# led-headlamp.net
KiCad netlist of a schematic drawn in EAGLE
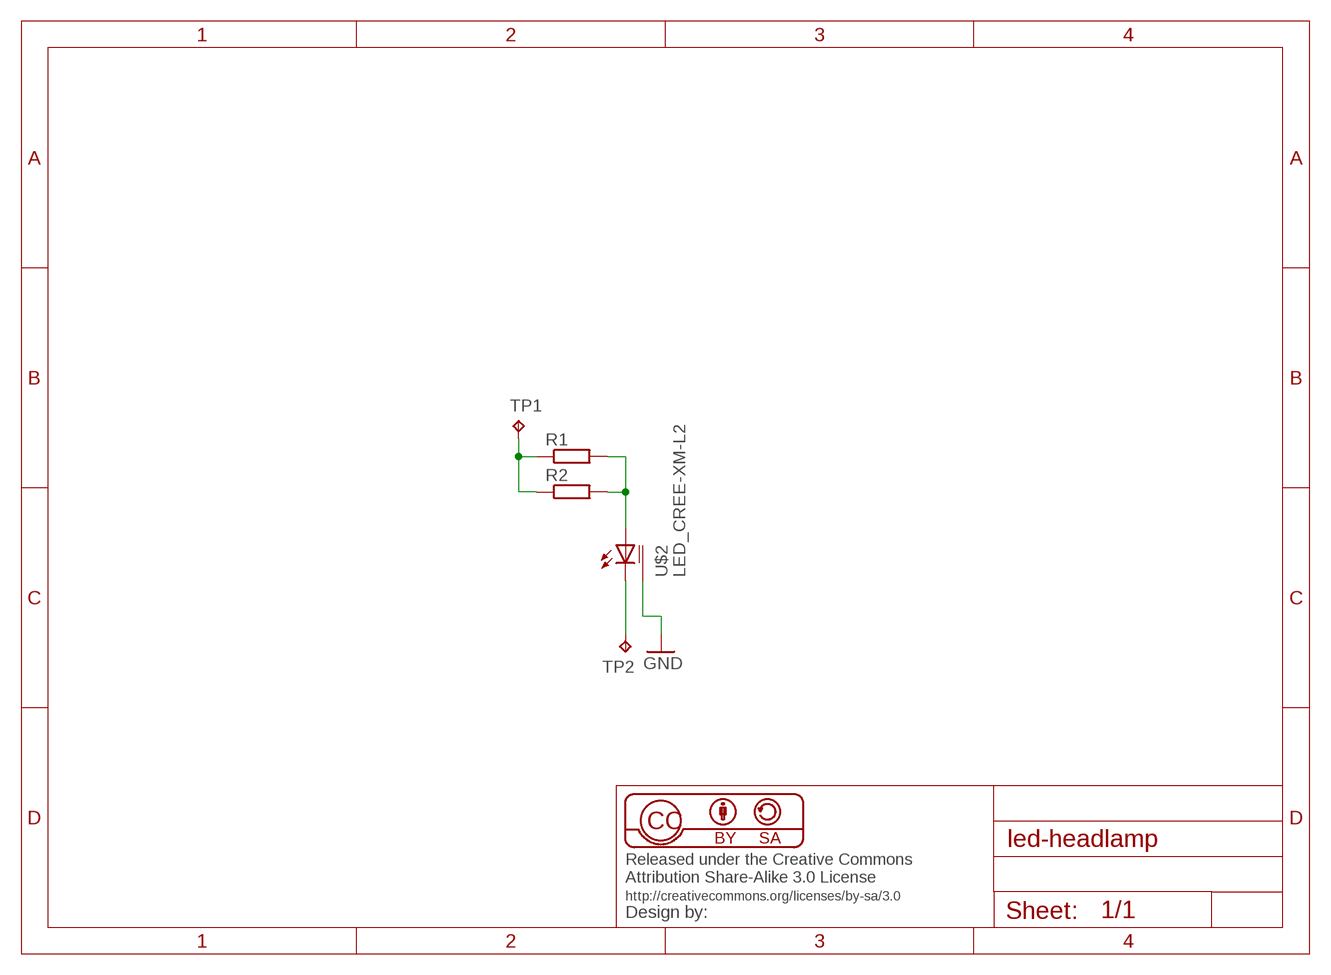
[diagram p0: schematic, sheet 1]

(export (version "E")
  (design (tool "Eeschema 10.0.6"))
  (components
    (comp (ref "R1")
      (value "R-EU_R0805")
      (footprint "eagle-import:R0805")
      (libsource (lib "eagle-import") (part "R-EU_R0805"))
    )
    (comp (ref "R2")
      (value "R-EU_R0805")
      (footprint "eagle-import:R0805")
      (libsource (lib "eagle-import") (part "R-EU_R0805"))
    )
    (comp (ref "TP1")
      (value "TPTP18R")
      (footprint "eagle-import:TP18R")
      (libsource (lib "eagle-import") (part "TPTP18R"))
    )
    (comp (ref "TP2")
      (value "TPTP18R")
      (footprint "eagle-import:TP18R")
      (libsource (lib "eagle-import") (part "TPTP18R"))
    )
    (comp (ref "U$2")
      (value "LED_CREE-XM-L2")
      (footprint "eagle-import:XLAMP_5X5")
      (libsource (lib "eagle-import") (part "LED_CREE-XM-L2"))
    )
  )
  (nets
    (net (code "1") (name "GND") (class "Default")
      (node (ref "U$2") (pin "TH") (pinfunction "TH_TH") (pintype "passive"))
    )
    (net (code "2") (name "Net-(R1-Pad1)") (class "Default")
      (node (ref "R1") (pin "1") (pinfunction "1_1") (pintype "passive"))
      (node (ref "R2") (pin "1") (pinfunction "1_1") (pintype "passive"))
      (node (ref "TP1") (pin "TP") (pinfunction "TP_TP") (pintype "input"))
    )
    (net (code "3") (name "Net-(R1-Pad2)") (class "Default")
      (node (ref "R1") (pin "2") (pinfunction "2_2") (pintype "passive"))
      (node (ref "R2") (pin "2") (pinfunction "2_2") (pintype "passive"))
      (node (ref "U$2") (pin "A") (pinfunction "A_A") (pintype "passive"))
    )
    (net (code "4") (name "Net-(U$2-C)") (class "Default")
      (node (ref "TP2") (pin "TP") (pinfunction "TP_TP") (pintype "input"))
      (node (ref "U$2") (pin "K") (pinfunction "C_K") (pintype "passive"))
    )
  )
)
